# ApHSC.net
KiCad netlist of a schematic drawn in EAGLE
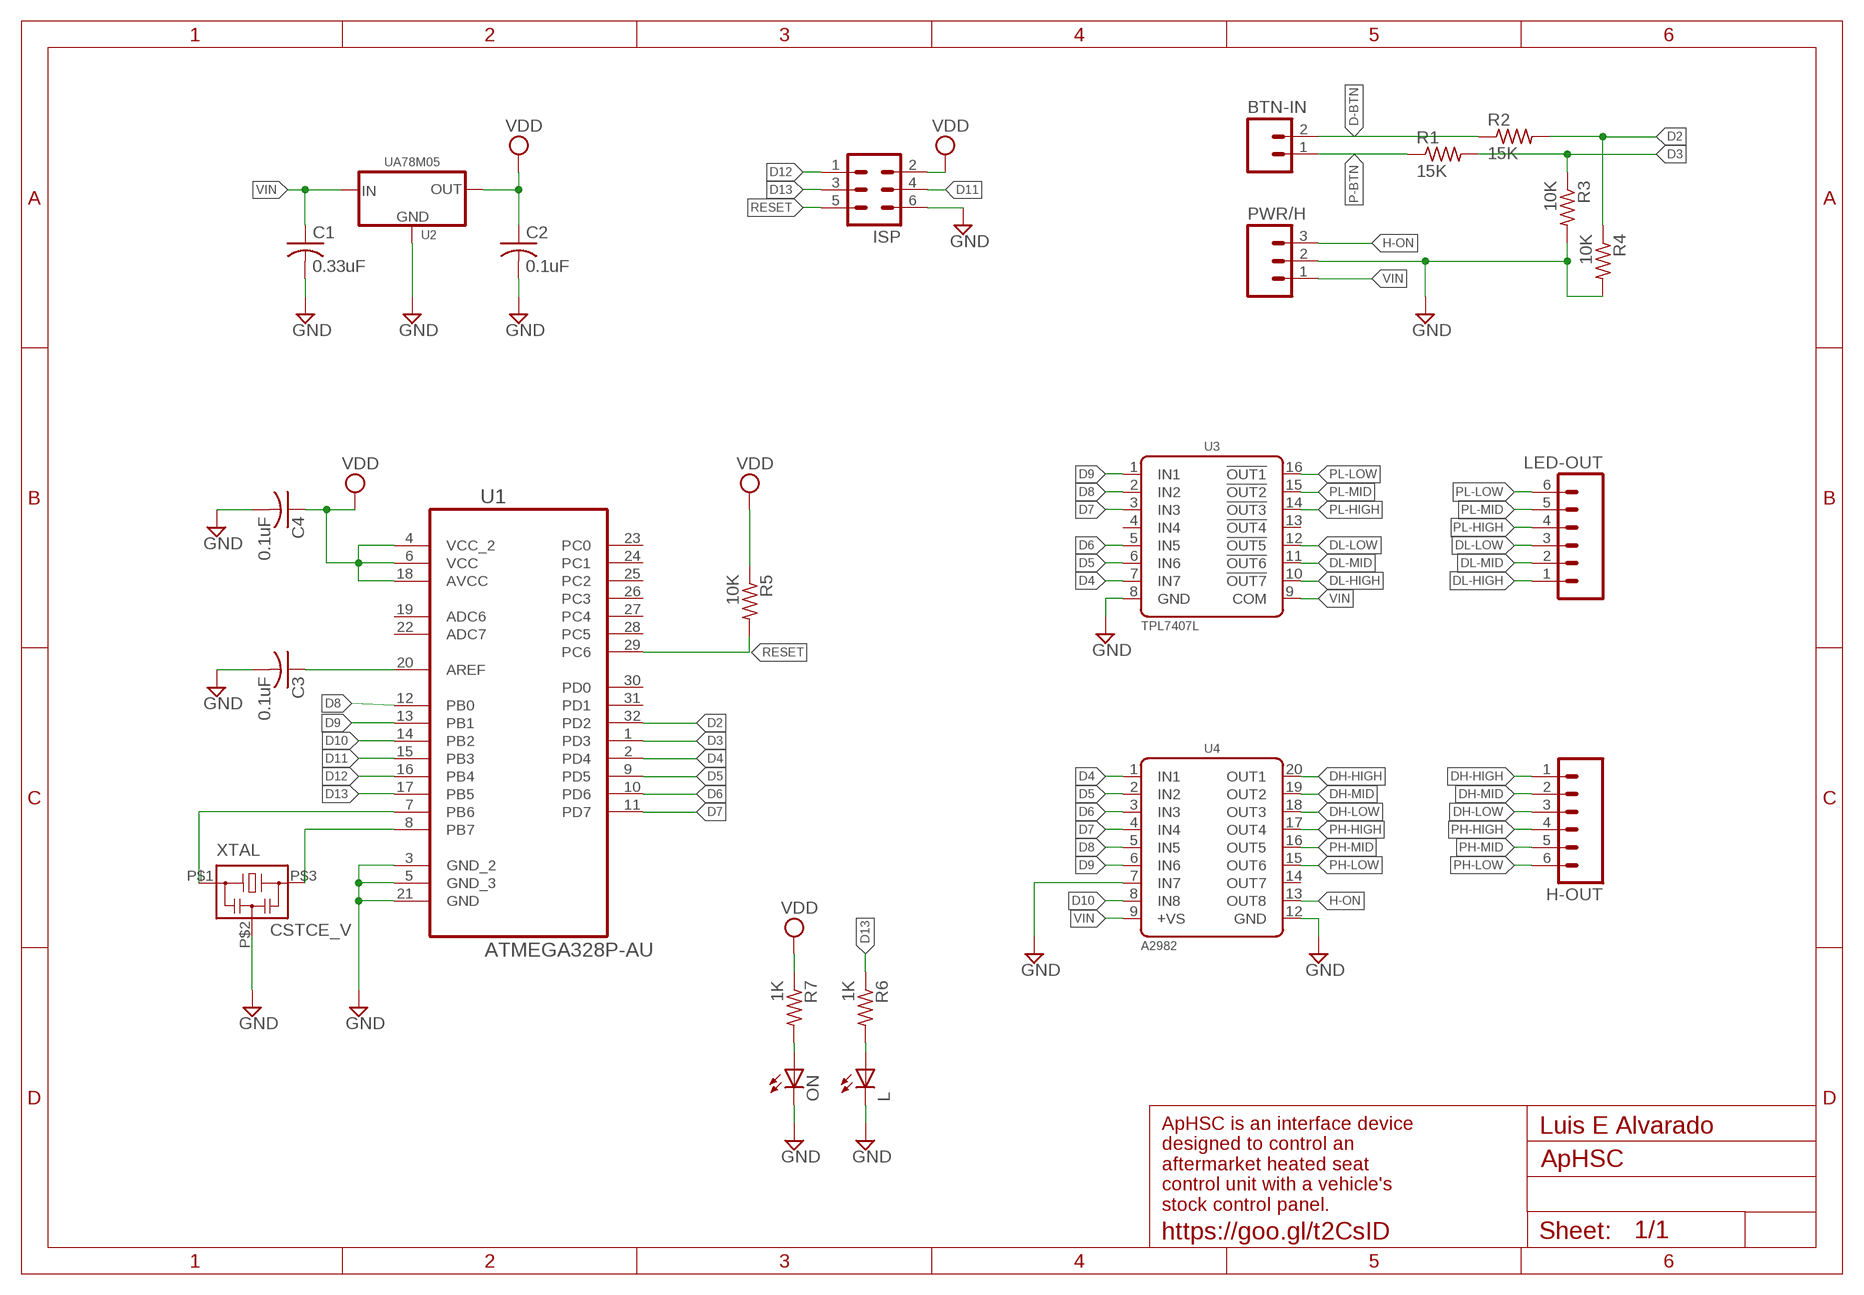
[diagram p0: schematic, sheet 1]

(export (version "E")
  (design (tool "Eeschema 10.0.6"))
  (components
    (comp (ref "BTN-IN")
      (value "M02PTH")
      (footprint "eagle-import:1X02")
      (libsource (lib "eagle-import") (part "M02PTH"))
    )
    (comp (ref "C1")
      (value "0.33uF")
      (footprint "eagle-import:C0603")
      (libsource (lib "eagle-import") (part "C-USC0603"))
    )
    (comp (ref "C2")
      (value "0.1uF")
      (footprint "eagle-import:C0603")
      (libsource (lib "eagle-import") (part "C-USC0603"))
    )
    (comp (ref "C3")
      (value "0.1uF")
      (footprint "eagle-import:C0603")
      (libsource (lib "eagle-import") (part "C-USC0603"))
    )
    (comp (ref "C4")
      (value "0.1uF")
      (footprint "eagle-import:C0603")
      (libsource (lib "eagle-import") (part "C-USC0603"))
    )
    (comp (ref "H-OUT")
      (value "M06SIP")
      (footprint "eagle-import:1X06")
      (libsource (lib "eagle-import") (part "M06SIP"))
    )
    (comp (ref "ISP")
      (value "MA03-2")
      (footprint "eagle-import:MA03-2")
      (libsource (lib "eagle-import") (part "MA03-2"))
    )
    (comp (ref "L")
      (value "LEDCHIP-LED0603")
      (footprint "eagle-import:CHIP-LED0603")
      (libsource (lib "eagle-import") (part "LEDCHIP-LED0603"))
    )
    (comp (ref "LED-OUT")
      (value "M06SIP")
      (footprint "eagle-import:1X06")
      (libsource (lib "eagle-import") (part "M06SIP"))
    )
    (comp (ref "ON")
      (value "LEDCHIP-LED0603")
      (footprint "eagle-import:CHIP-LED0603")
      (libsource (lib "eagle-import") (part "LEDCHIP-LED0603"))
    )
    (comp (ref "PWR/H")
      (value "M03PTH")
      (footprint "eagle-import:1X03")
      (libsource (lib "eagle-import") (part "M03PTH"))
    )
    (comp (ref "R1")
      (value "15K")
      (footprint "eagle-import:R0603")
      (libsource (lib "eagle-import") (part "R-US_R0603"))
    )
    (comp (ref "R2")
      (value "15K")
      (footprint "eagle-import:R0603")
      (libsource (lib "eagle-import") (part "R-US_R0603"))
    )
    (comp (ref "R3")
      (value "10K")
      (footprint "eagle-import:R0603")
      (libsource (lib "eagle-import") (part "R-US_R0603"))
    )
    (comp (ref "R4")
      (value "10K")
      (footprint "eagle-import:R0603")
      (libsource (lib "eagle-import") (part "R-US_R0603"))
    )
    (comp (ref "R5")
      (value "10K")
      (footprint "eagle-import:R0603")
      (libsource (lib "eagle-import") (part "R-US_R0603"))
    )
    (comp (ref "R6")
      (value "1K")
      (footprint "eagle-import:R0603")
      (libsource (lib "eagle-import") (part "R-US_R0603"))
    )
    (comp (ref "R7")
      (value "1K")
      (footprint "eagle-import:R0603")
      (libsource (lib "eagle-import") (part "R-US_R0603"))
    )
    (comp (ref "U1")
      (value "ATMEGA328P-AU")
      (footprint "eagle-import:QFP80P900X900X120-32N")
      (libsource (lib "eagle-import") (part "ATMEGA328P-AU"))
    )
    (comp (ref "U2")
      (value "UA78M05")
      (footprint "eagle-import:SOT223")
      (libsource (lib "eagle-import") (part "UA78M05"))
    )
    (comp (ref "U3")
      (value "TPL7407L")
      (footprint "eagle-import:SOIC16N")
      (libsource (lib "eagle-import") (part "TPL7407L"))
    )
    (comp (ref "U4")
      (value "A2982")
      (footprint "eagle-import:SOIC20W")
      (libsource (lib "eagle-import") (part "A2982"))
    )
    (comp (ref "XTAL")
      (value "CSTCE_V")
      (footprint "eagle-import:CSTCE_V")
      (libsource (lib "eagle-import") (part "CSTCE_V"))
    )
  )
  (nets
    (net (code "1") (name "D-BTN") (class "Default")
      (node (ref "BTN-IN") (pin "2") (pinfunction "2_2") (pintype "passive"))
      (node (ref "R2") (pin "1") (pinfunction "1_1") (pintype "passive"))
    )
    (net (code "2") (name "D2") (class "Default")
      (node (ref "R2") (pin "2") (pinfunction "2_2") (pintype "passive"))
      (node (ref "R4") (pin "1") (pinfunction "1_1") (pintype "passive"))
      (node (ref "U1") (pin "32") (pinfunction "PD2_32") (pintype "bidirectional"))
    )
    (net (code "3") (name "D3") (class "Default")
      (node (ref "R1") (pin "2") (pinfunction "2_2") (pintype "passive"))
      (node (ref "R3") (pin "1") (pinfunction "1_1") (pintype "passive"))
      (node (ref "U1") (pin "1") (pinfunction "PD3_1") (pintype "bidirectional"))
    )
    (net (code "4") (name "D4") (class "Default")
      (node (ref "U1") (pin "2") (pinfunction "PD4_2") (pintype "bidirectional"))
      (node (ref "U3") (pin "7") (pinfunction "IN7_7") (pintype "bidirectional"))
      (node (ref "U4") (pin "1") (pinfunction "IN1_1") (pintype "bidirectional"))
    )
    (net (code "5") (name "D5") (class "Default")
      (node (ref "U1") (pin "9") (pinfunction "PD5_9") (pintype "bidirectional"))
      (node (ref "U3") (pin "6") (pinfunction "IN6_6") (pintype "bidirectional"))
      (node (ref "U4") (pin "2") (pinfunction "IN2_2") (pintype "bidirectional"))
    )
    (net (code "6") (name "D6") (class "Default")
      (node (ref "U1") (pin "10") (pinfunction "PD6_10") (pintype "bidirectional"))
      (node (ref "U3") (pin "5") (pinfunction "IN5_5") (pintype "bidirectional"))
      (node (ref "U4") (pin "3") (pinfunction "IN3_3") (pintype "bidirectional"))
    )
    (net (code "7") (name "D7") (class "Default")
      (node (ref "U1") (pin "11") (pinfunction "PD7_11") (pintype "bidirectional"))
      (node (ref "U3") (pin "3") (pinfunction "IN3_3") (pintype "bidirectional"))
      (node (ref "U4") (pin "4") (pinfunction "IN4_4") (pintype "bidirectional"))
    )
    (net (code "8") (name "D8") (class "Default")
      (node (ref "U1") (pin "12") (pinfunction "PB0_12") (pintype "bidirectional"))
      (node (ref "U3") (pin "2") (pinfunction "IN2_2") (pintype "bidirectional"))
      (node (ref "U4") (pin "5") (pinfunction "IN5_5") (pintype "bidirectional"))
    )
    (net (code "9") (name "D9") (class "Default")
      (node (ref "U1") (pin "13") (pinfunction "PB1_13") (pintype "bidirectional"))
      (node (ref "U3") (pin "1") (pinfunction "IN1_1") (pintype "bidirectional"))
      (node (ref "U4") (pin "6") (pinfunction "IN6_6") (pintype "bidirectional"))
    )
    (net (code "10") (name "D10") (class "Default")
      (node (ref "U1") (pin "14") (pinfunction "PB2_14") (pintype "bidirectional"))
      (node (ref "U4") (pin "8") (pinfunction "IN8_8") (pintype "bidirectional"))
    )
    (net (code "11") (name "D11") (class "Default")
      (node (ref "ISP") (pin "4") (pinfunction "4_4") (pintype "passive"))
      (node (ref "U1") (pin "15") (pinfunction "PB3_15") (pintype "bidirectional"))
    )
    (net (code "12") (name "D12") (class "Default")
      (node (ref "ISP") (pin "1") (pinfunction "1_1") (pintype "passive"))
      (node (ref "U1") (pin "16") (pinfunction "PB4_16") (pintype "bidirectional"))
    )
    (net (code "13") (name "D13") (class "Default")
      (node (ref "ISP") (pin "3") (pinfunction "3_3") (pintype "passive"))
      (node (ref "R6") (pin "1") (pinfunction "1_1") (pintype "passive"))
      (node (ref "U1") (pin "17") (pinfunction "PB5_17") (pintype "bidirectional"))
    )
    (net (code "14") (name "DH-HIGH") (class "Default")
      (node (ref "H-OUT") (pin "1") (pinfunction "1_1") (pintype "passive"))
      (node (ref "U4") (pin "20") (pinfunction "OUT1_20") (pintype "bidirectional"))
    )
    (net (code "15") (name "DH-LOW") (class "Default")
      (node (ref "H-OUT") (pin "3") (pinfunction "3_3") (pintype "passive"))
      (node (ref "U4") (pin "18") (pinfunction "OUT3_18") (pintype "bidirectional"))
    )
    (net (code "16") (name "DH-MID") (class "Default")
      (node (ref "H-OUT") (pin "2") (pinfunction "2_2") (pintype "passive"))
      (node (ref "U4") (pin "19") (pinfunction "OUT2_19") (pintype "bidirectional"))
    )
    (net (code "17") (name "DL-HIGH") (class "Default")
      (node (ref "LED-OUT") (pin "1") (pinfunction "1_1") (pintype "passive"))
      (node (ref "U3") (pin "10") (pinfunction "~{OUT7}_10") (pintype "bidirectional"))
    )
    (net (code "18") (name "DL-LOW") (class "Default")
      (node (ref "LED-OUT") (pin "3") (pinfunction "3_3") (pintype "passive"))
      (node (ref "U3") (pin "12") (pinfunction "~{OUT5}_12") (pintype "bidirectional"))
    )
    (net (code "19") (name "DL-MID") (class "Default")
      (node (ref "LED-OUT") (pin "2") (pinfunction "2_2") (pintype "passive"))
      (node (ref "U3") (pin "11") (pinfunction "~{OUT6}_11") (pintype "bidirectional"))
    )
    (net (code "20") (name "GND") (class "Default")
      (node (ref "C1") (pin "2") (pinfunction "2_2") (pintype "passive"))
      (node (ref "C2") (pin "2") (pinfunction "2_2") (pintype "passive"))
      (node (ref "C3") (pin "2") (pinfunction "2_2") (pintype "passive"))
      (node (ref "C4") (pin "2") (pinfunction "2_2") (pintype "passive"))
      (node (ref "ISP") (pin "6") (pinfunction "6_6") (pintype "passive"))
      (node (ref "L") (pin "C") (pinfunction "C_C") (pintype "passive"))
      (node (ref "ON") (pin "C") (pinfunction "C_C") (pintype "passive"))
      (node (ref "PWR/H") (pin "2") (pinfunction "2_2") (pintype "passive"))
      (node (ref "R3") (pin "2") (pinfunction "2_2") (pintype "passive"))
      (node (ref "R4") (pin "2") (pinfunction "2_2") (pintype "passive"))
      (node (ref "U1") (pin "21") (pinfunction "GND_21") (pintype "passive"))
      (node (ref "U1") (pin "3") (pinfunction "GND_2_3") (pintype "passive"))
      (node (ref "U1") (pin "5") (pinfunction "GND_3_5") (pintype "passive"))
      (node (ref "U2") (pin "2") (pinfunction "GND_2") (pintype "input"))
      (node (ref "U3") (pin "8") (pinfunction "GND_8") (pintype "bidirectional"))
      (node (ref "U4") (pin "12") (pinfunction "GND_12") (pintype "bidirectional"))
      (node (ref "U4") (pin "7") (pinfunction "IN7_7") (pintype "bidirectional"))
      (node (ref "XTAL") (pin "P$2") (pinfunction "2_P$2") (pintype "passive"))
    )
    (net (code "21") (name "H-ON") (class "Default")
      (node (ref "PWR/H") (pin "3") (pinfunction "3_3") (pintype "passive"))
      (node (ref "U4") (pin "13") (pinfunction "OUT8_13") (pintype "bidirectional"))
    )
    (net (code "22") (name "Net-(L-PadA)") (class "Default")
      (node (ref "L") (pin "A") (pinfunction "A_A") (pintype "passive"))
      (node (ref "R6") (pin "2") (pinfunction "2_2") (pintype "passive"))
    )
    (net (code "23") (name "Net-(ON-PadA)") (class "Default")
      (node (ref "ON") (pin "A") (pinfunction "A_A") (pintype "passive"))
      (node (ref "R7") (pin "2") (pinfunction "2_2") (pintype "passive"))
    )
    (net (code "24") (name "Net-(U1-AREF)") (class "Default")
      (node (ref "C3") (pin "1") (pinfunction "1_1") (pintype "passive"))
      (node (ref "U1") (pin "20") (pinfunction "AREF_20") (pintype "input"))
    )
    (net (code "25") (name "Net-(U1-PB6)") (class "Default")
      (node (ref "U1") (pin "7") (pinfunction "PB6_7") (pintype "bidirectional"))
      (node (ref "XTAL") (pin "P$1") (pinfunction "1_P$1") (pintype "passive"))
    )
    (net (code "26") (name "Net-(U1-PB7)") (class "Default")
      (node (ref "U1") (pin "8") (pinfunction "PB7_8") (pintype "bidirectional"))
      (node (ref "XTAL") (pin "P$3") (pinfunction "3_P$3") (pintype "passive"))
    )
    (net (code "27") (name "P-BTN") (class "Default")
      (node (ref "BTN-IN") (pin "1") (pinfunction "1_1") (pintype "passive"))
      (node (ref "R1") (pin "1") (pinfunction "1_1") (pintype "passive"))
    )
    (net (code "28") (name "PH-HIGH") (class "Default")
      (node (ref "H-OUT") (pin "4") (pinfunction "4_4") (pintype "passive"))
      (node (ref "U4") (pin "17") (pinfunction "OUT4_17") (pintype "bidirectional"))
    )
    (net (code "29") (name "PH-LOW") (class "Default")
      (node (ref "H-OUT") (pin "6") (pinfunction "6_6") (pintype "passive"))
      (node (ref "U4") (pin "15") (pinfunction "OUT6_15") (pintype "bidirectional"))
    )
    (net (code "30") (name "PH-MID") (class "Default")
      (node (ref "H-OUT") (pin "5") (pinfunction "5_5") (pintype "passive"))
      (node (ref "U4") (pin "16") (pinfunction "OUT5_16") (pintype "bidirectional"))
    )
    (net (code "31") (name "PL-HIGH") (class "Default")
      (node (ref "LED-OUT") (pin "4") (pinfunction "4_4") (pintype "passive"))
      (node (ref "U3") (pin "14") (pinfunction "~{OUT3}_14") (pintype "bidirectional"))
    )
    (net (code "32") (name "PL-LOW") (class "Default")
      (node (ref "LED-OUT") (pin "6") (pinfunction "6_6") (pintype "passive"))
      (node (ref "U3") (pin "16") (pinfunction "~{OUT1}_16") (pintype "bidirectional"))
    )
    (net (code "33") (name "PL-MID") (class "Default")
      (node (ref "LED-OUT") (pin "5") (pinfunction "5_5") (pintype "passive"))
      (node (ref "U3") (pin "15") (pinfunction "~{OUT2}_15") (pintype "bidirectional"))
    )
    (net (code "34") (name "RESET") (class "Default")
      (node (ref "ISP") (pin "5") (pinfunction "5_5") (pintype "passive"))
      (node (ref "R5") (pin "2") (pinfunction "2_2") (pintype "passive"))
      (node (ref "U1") (pin "29") (pinfunction "PC6_29") (pintype "bidirectional"))
    )
    (net (code "35") (name "VDD") (class "Default")
      (node (ref "C2") (pin "1") (pinfunction "1_1") (pintype "passive"))
      (node (ref "C4") (pin "1") (pinfunction "1_1") (pintype "passive"))
      (node (ref "ISP") (pin "2") (pinfunction "2_2") (pintype "passive"))
      (node (ref "R5") (pin "1") (pinfunction "1_1") (pintype "passive"))
      (node (ref "R7") (pin "1") (pinfunction "1_1") (pintype "passive"))
      (node (ref "U1") (pin "18") (pinfunction "AVCC_18") (pintype "power_in"))
      (node (ref "U1") (pin "4") (pinfunction "VCC_2_4") (pintype "power_in"))
      (node (ref "U1") (pin "6") (pinfunction "VCC_6") (pintype "power_in"))
      (node (ref "U2") (pin "3") (pinfunction "OUT_3") (pintype "passive"))
    )
    (net (code "36") (name "VIN") (class "Default")
      (node (ref "C1") (pin "1") (pinfunction "1_1") (pintype "passive"))
      (node (ref "PWR/H") (pin "1") (pinfunction "1_1") (pintype "passive"))
      (node (ref "U2") (pin "1") (pinfunction "IN_1") (pintype "input"))
      (node (ref "U3") (pin "9") (pinfunction "COM_9") (pintype "bidirectional"))
      (node (ref "U4") (pin "9") (pinfunction "+VS_9") (pintype "bidirectional"))
    )
    (net (code "37") (name "unconnected-(U1-ADC6-Pad19)") (class "Default")
      (node (ref "U1") (pin "19") (pinfunction "ADC6_19") (pintype "input"))
    )
    (net (code "38") (name "unconnected-(U1-ADC7-Pad22)") (class "Default")
      (node (ref "U1") (pin "22") (pinfunction "ADC7_22") (pintype "input"))
    )
    (net (code "39") (name "unconnected-(U1-PC0-Pad23)") (class "Default")
      (node (ref "U1") (pin "23") (pinfunction "PC0_23") (pintype "bidirectional"))
    )
    (net (code "40") (name "unconnected-(U1-PC1-Pad24)") (class "Default")
      (node (ref "U1") (pin "24") (pinfunction "PC1_24") (pintype "bidirectional"))
    )
    (net (code "41") (name "unconnected-(U1-PC2-Pad25)") (class "Default")
      (node (ref "U1") (pin "25") (pinfunction "PC2_25") (pintype "bidirectional"))
    )
    (net (code "42") (name "unconnected-(U1-PC3-Pad26)") (class "Default")
      (node (ref "U1") (pin "26") (pinfunction "PC3_26") (pintype "bidirectional"))
    )
    (net (code "43") (name "unconnected-(U1-PC4-Pad27)") (class "Default")
      (node (ref "U1") (pin "27") (pinfunction "PC4_27") (pintype "bidirectional"))
    )
    (net (code "44") (name "unconnected-(U1-PC5-Pad28)") (class "Default")
      (node (ref "U1") (pin "28") (pinfunction "PC5_28") (pintype "bidirectional"))
    )
    (net (code "45") (name "unconnected-(U1-PD0-Pad30)") (class "Default")
      (node (ref "U1") (pin "30") (pinfunction "PD0_30") (pintype "bidirectional"))
    )
    (net (code "46") (name "unconnected-(U1-PD1-Pad31)") (class "Default")
      (node (ref "U1") (pin "31") (pinfunction "PD1_31") (pintype "bidirectional"))
    )
    (net (code "47") (name "unconnected-(U3-IN4-Pad4)") (class "Default")
      (node (ref "U3") (pin "4") (pinfunction "IN4_4") (pintype "bidirectional"))
    )
    (net (code "48") (name "unconnected-(U3-~{OUT4}-Pad13)") (class "Default")
      (node (ref "U3") (pin "13") (pinfunction "~{OUT4}_13") (pintype "bidirectional"))
    )
    (net (code "49") (name "unconnected-(U4-OUT7-Pad14)") (class "Default")
      (node (ref "U4") (pin "14") (pinfunction "OUT7_14") (pintype "bidirectional"))
    )
  )
)
